# schematic1.net
KiCad netlist of a schematic drawn in EAGLE
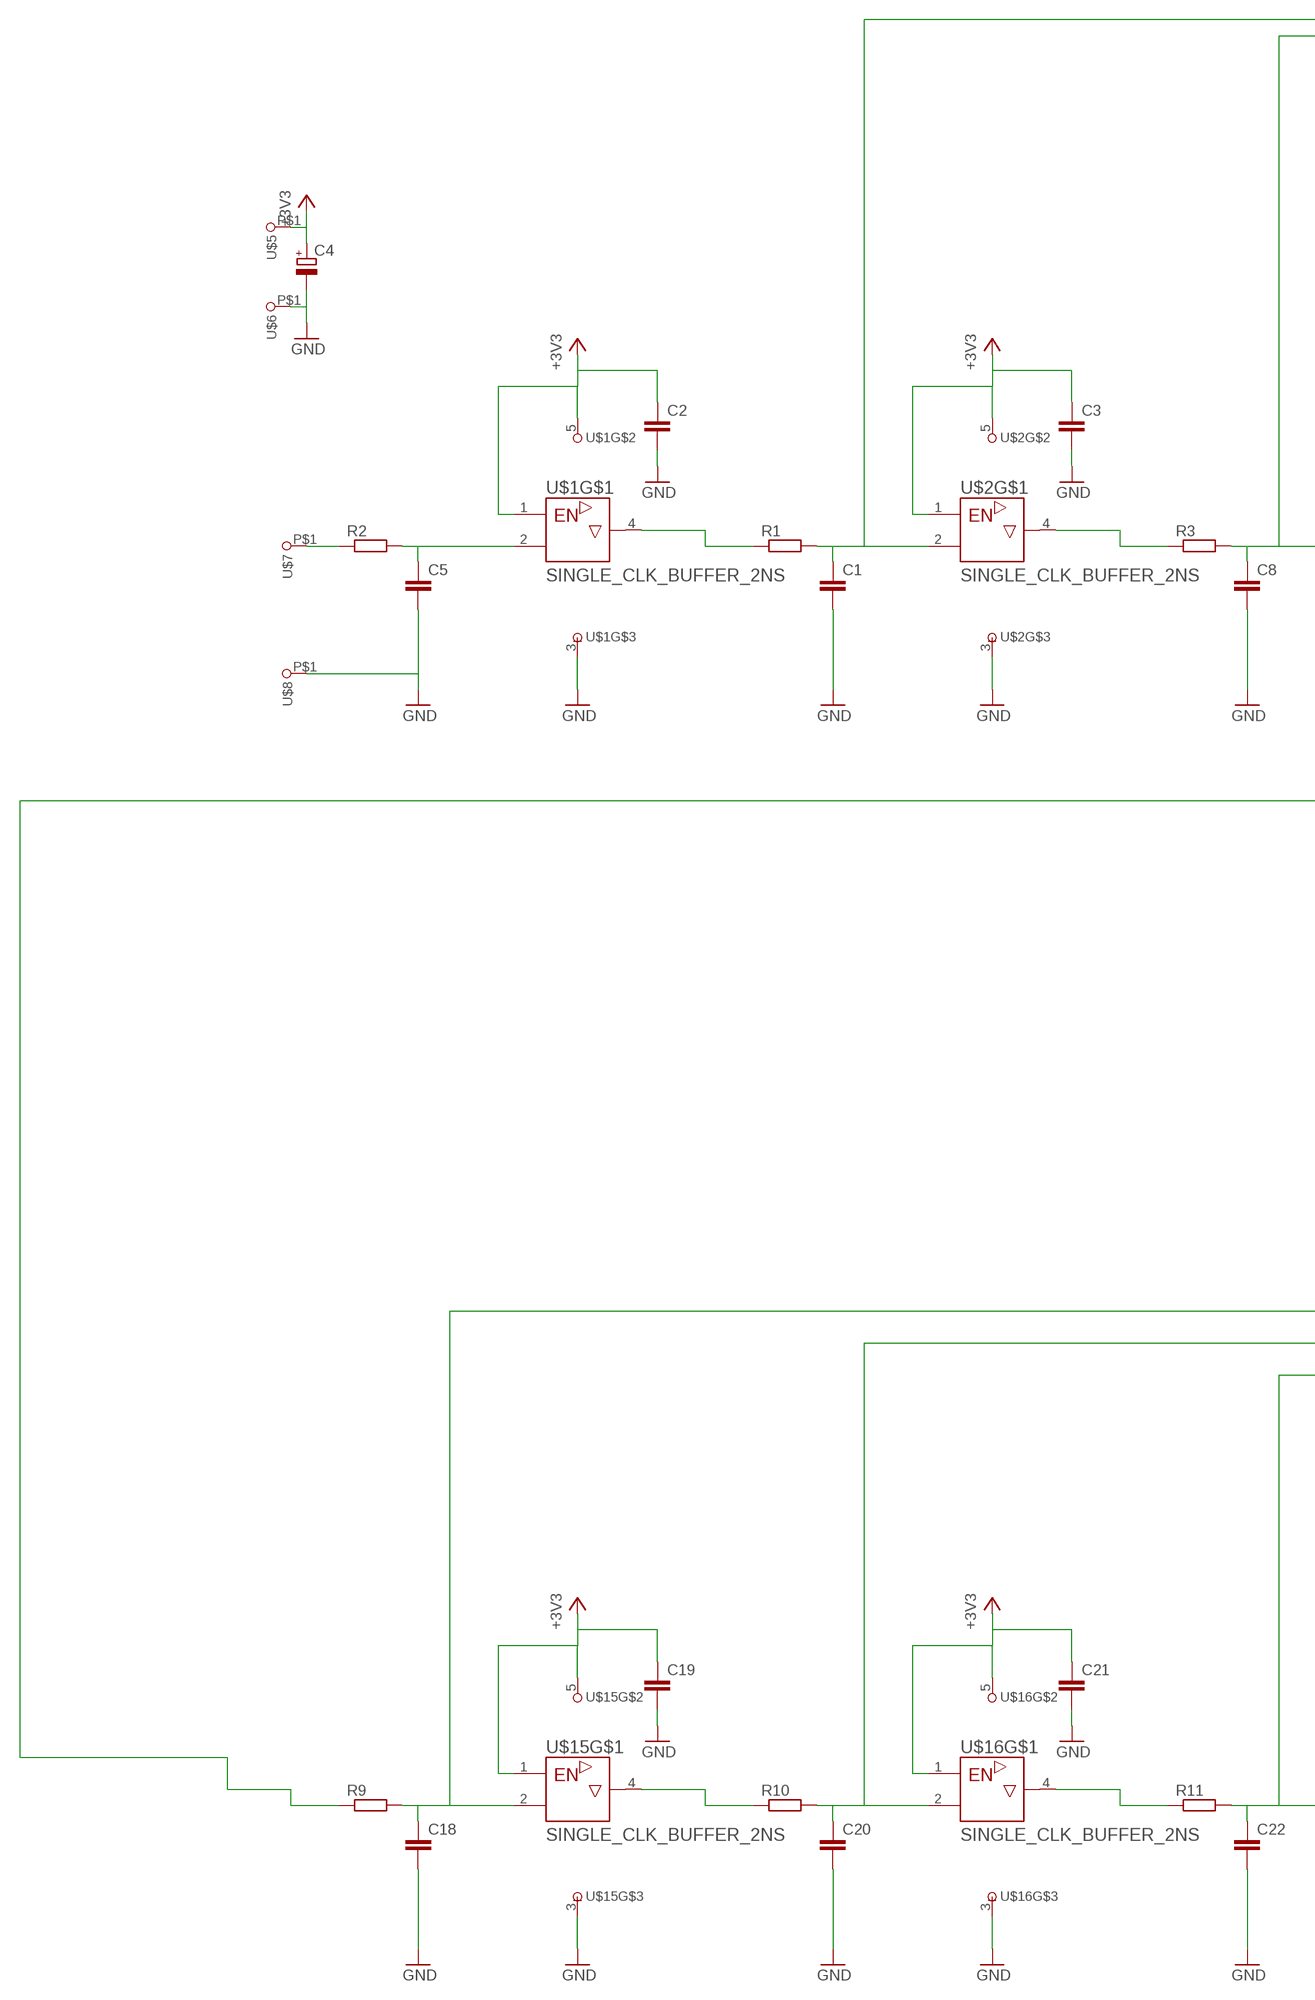
[diagram p0: schematic, sheet 1, part 1 of 2]
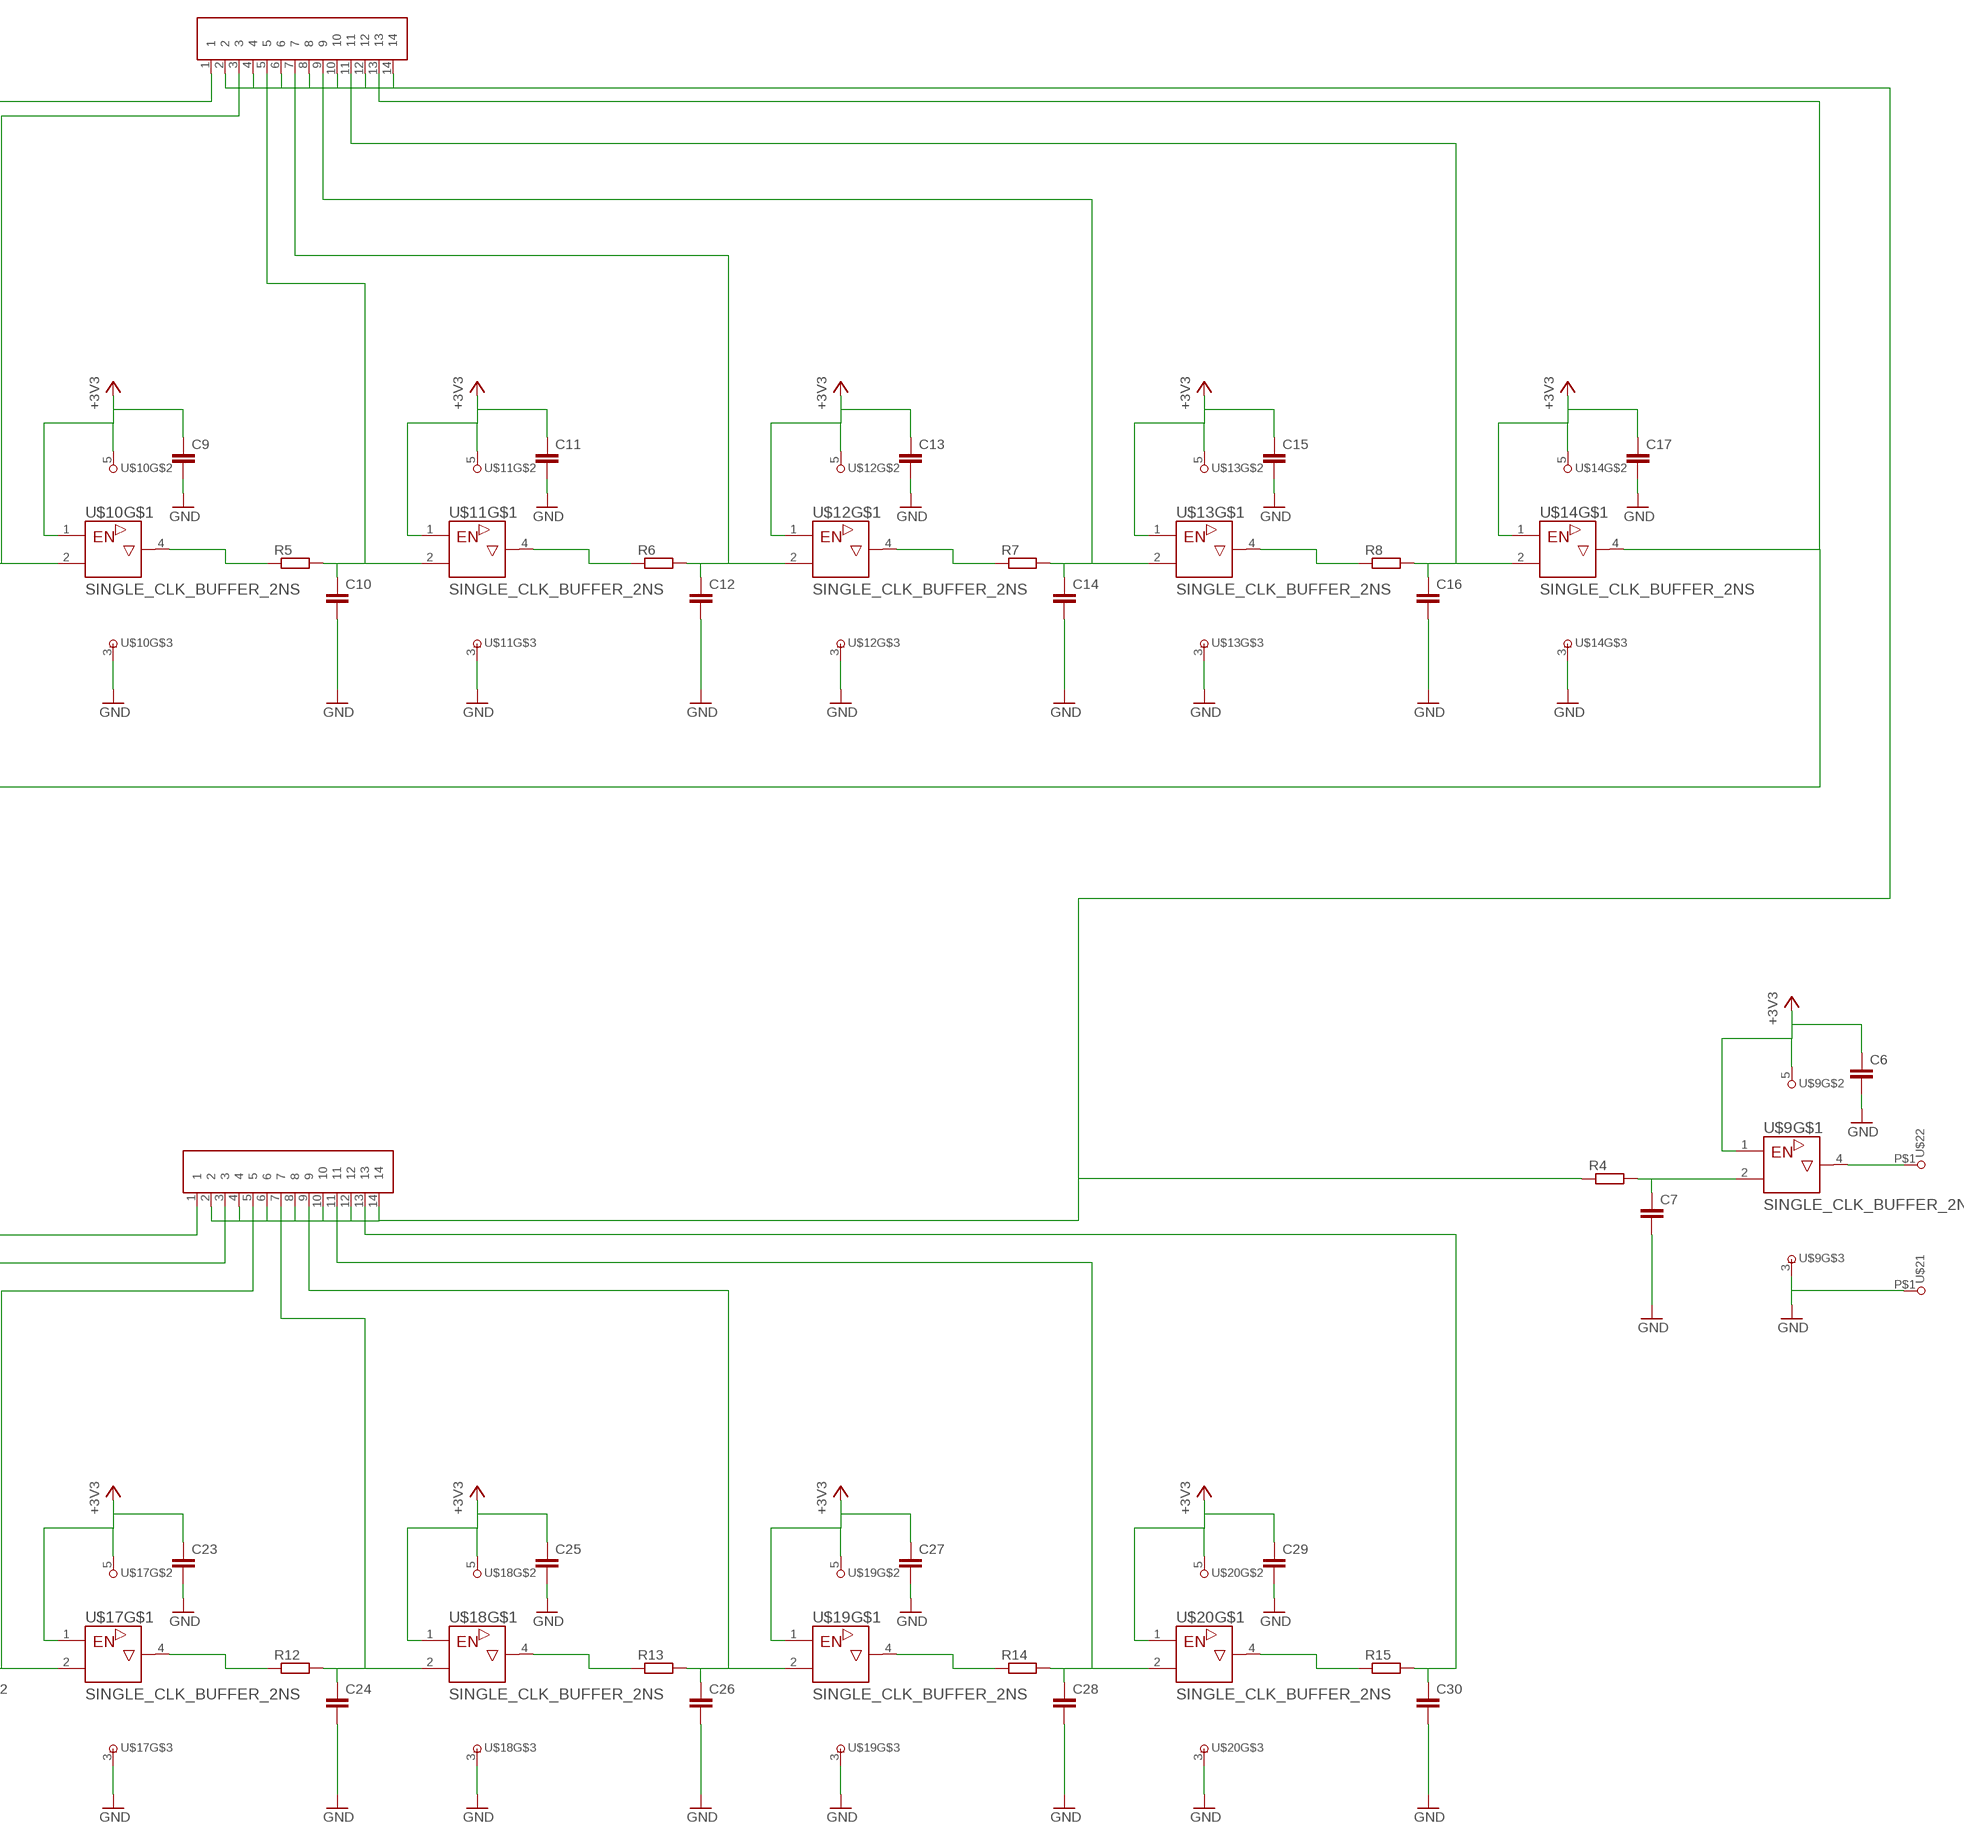
[diagram p1: schematic, sheet 1, part 2 of 2]

(export (version "E")
  (design (tool "Eeschema 10.0.6"))
  (components
    (comp (ref "C1")
      (value "C-EUC0603")
      (footprint "eagle-import:C0603")
      (libsource (lib "eagle-import") (part "C-EUC0603"))
    )
    (comp (ref "C2")
      (value "C-EUC0805")
      (footprint "eagle-import:C0805")
      (libsource (lib "eagle-import") (part "C-EUC0805"))
    )
    (comp (ref "C3")
      (value "C-EUC0805")
      (footprint "eagle-import:C0805")
      (libsource (lib "eagle-import") (part "C-EUC0805"))
    )
    (comp (ref "C4")
      (value "CPOL-EUSMCD")
      (footprint "eagle-import:SMC_D")
      (libsource (lib "eagle-import") (part "CPOL-EUSMCD"))
    )
    (comp (ref "C5")
      (value "C-EUC0603")
      (footprint "eagle-import:C0603")
      (libsource (lib "eagle-import") (part "C-EUC0603"))
    )
    (comp (ref "C6")
      (value "C-EUC0805")
      (footprint "eagle-import:C0805")
      (libsource (lib "eagle-import") (part "C-EUC0805"))
    )
    (comp (ref "C7")
      (value "C-EUC0603")
      (footprint "eagle-import:C0603")
      (libsource (lib "eagle-import") (part "C-EUC0603"))
    )
    (comp (ref "C8")
      (value "C-EUC0603")
      (footprint "eagle-import:C0603")
      (libsource (lib "eagle-import") (part "C-EUC0603"))
    )
    (comp (ref "C9")
      (value "C-EUC0805")
      (footprint "eagle-import:C0805")
      (libsource (lib "eagle-import") (part "C-EUC0805"))
    )
    (comp (ref "C10")
      (value "C-EUC0603")
      (footprint "eagle-import:C0603")
      (libsource (lib "eagle-import") (part "C-EUC0603"))
    )
    (comp (ref "C11")
      (value "C-EUC0805")
      (footprint "eagle-import:C0805")
      (libsource (lib "eagle-import") (part "C-EUC0805"))
    )
    (comp (ref "C12")
      (value "C-EUC0603")
      (footprint "eagle-import:C0603")
      (libsource (lib "eagle-import") (part "C-EUC0603"))
    )
    (comp (ref "C13")
      (value "C-EUC0805")
      (footprint "eagle-import:C0805")
      (libsource (lib "eagle-import") (part "C-EUC0805"))
    )
    (comp (ref "C14")
      (value "C-EUC0603")
      (footprint "eagle-import:C0603")
      (libsource (lib "eagle-import") (part "C-EUC0603"))
    )
    (comp (ref "C15")
      (value "C-EUC0805")
      (footprint "eagle-import:C0805")
      (libsource (lib "eagle-import") (part "C-EUC0805"))
    )
    (comp (ref "C16")
      (value "C-EUC0603")
      (footprint "eagle-import:C0603")
      (libsource (lib "eagle-import") (part "C-EUC0603"))
    )
    (comp (ref "C17")
      (value "C-EUC0805")
      (footprint "eagle-import:C0805")
      (libsource (lib "eagle-import") (part "C-EUC0805"))
    )
    (comp (ref "C18")
      (value "C-EUC0603")
      (footprint "eagle-import:C0603")
      (libsource (lib "eagle-import") (part "C-EUC0603"))
    )
    (comp (ref "C19")
      (value "C-EUC0805")
      (footprint "eagle-import:C0805")
      (libsource (lib "eagle-import") (part "C-EUC0805"))
    )
    (comp (ref "C20")
      (value "C-EUC0603")
      (footprint "eagle-import:C0603")
      (libsource (lib "eagle-import") (part "C-EUC0603"))
    )
    (comp (ref "C21")
      (value "C-EUC0805")
      (footprint "eagle-import:C0805")
      (libsource (lib "eagle-import") (part "C-EUC0805"))
    )
    (comp (ref "C22")
      (value "C-EUC0603")
      (footprint "eagle-import:C0603")
      (libsource (lib "eagle-import") (part "C-EUC0603"))
    )
    (comp (ref "C23")
      (value "C-EUC0805")
      (footprint "eagle-import:C0805")
      (libsource (lib "eagle-import") (part "C-EUC0805"))
    )
    (comp (ref "C24")
      (value "C-EUC0603")
      (footprint "eagle-import:C0603")
      (libsource (lib "eagle-import") (part "C-EUC0603"))
    )
    (comp (ref "C25")
      (value "C-EUC0805")
      (footprint "eagle-import:C0805")
      (libsource (lib "eagle-import") (part "C-EUC0805"))
    )
    (comp (ref "C26")
      (value "C-EUC0603")
      (footprint "eagle-import:C0603")
      (libsource (lib "eagle-import") (part "C-EUC0603"))
    )
    (comp (ref "C27")
      (value "C-EUC0805")
      (footprint "eagle-import:C0805")
      (libsource (lib "eagle-import") (part "C-EUC0805"))
    )
    (comp (ref "C28")
      (value "C-EUC0603")
      (footprint "eagle-import:C0603")
      (libsource (lib "eagle-import") (part "C-EUC0603"))
    )
    (comp (ref "C29")
      (value "C-EUC0805")
      (footprint "eagle-import:C0805")
      (libsource (lib "eagle-import") (part "C-EUC0805"))
    )
    (comp (ref "C30")
      (value "C-EUC0603")
      (footprint "eagle-import:C0603")
      (libsource (lib "eagle-import") (part "C-EUC0603"))
    )
    (comp (ref "R1")
      (value "R-EU_R0603")
      (footprint "eagle-import:R0603")
      (libsource (lib "eagle-import") (part "R-EU_R0603"))
    )
    (comp (ref "R2")
      (value "R-EU_R0603")
      (footprint "eagle-import:R0603")
      (libsource (lib "eagle-import") (part "R-EU_R0603"))
    )
    (comp (ref "R3")
      (value "R-EU_R0603")
      (footprint "eagle-import:R0603")
      (libsource (lib "eagle-import") (part "R-EU_R0603"))
    )
    (comp (ref "R4")
      (value "R-EU_R0603")
      (footprint "eagle-import:R0603")
      (libsource (lib "eagle-import") (part "R-EU_R0603"))
    )
    (comp (ref "R5")
      (value "R-EU_R0603")
      (footprint "eagle-import:R0603")
      (libsource (lib "eagle-import") (part "R-EU_R0603"))
    )
    (comp (ref "R6")
      (value "R-EU_R0603")
      (footprint "eagle-import:R0603")
      (libsource (lib "eagle-import") (part "R-EU_R0603"))
    )
    (comp (ref "R7")
      (value "R-EU_R0603")
      (footprint "eagle-import:R0603")
      (libsource (lib "eagle-import") (part "R-EU_R0603"))
    )
    (comp (ref "R8")
      (value "R-EU_R0603")
      (footprint "eagle-import:R0603")
      (libsource (lib "eagle-import") (part "R-EU_R0603"))
    )
    (comp (ref "R9")
      (value "R-EU_R0603")
      (footprint "eagle-import:R0603")
      (libsource (lib "eagle-import") (part "R-EU_R0603"))
    )
    (comp (ref "R10")
      (value "R-EU_R0603")
      (footprint "eagle-import:R0603")
      (libsource (lib "eagle-import") (part "R-EU_R0603"))
    )
    (comp (ref "R11")
      (value "R-EU_R0603")
      (footprint "eagle-import:R0603")
      (libsource (lib "eagle-import") (part "R-EU_R0603"))
    )
    (comp (ref "R12")
      (value "R-EU_R0603")
      (footprint "eagle-import:R0603")
      (libsource (lib "eagle-import") (part "R-EU_R0603"))
    )
    (comp (ref "R13")
      (value "R-EU_R0603")
      (footprint "eagle-import:R0603")
      (libsource (lib "eagle-import") (part "R-EU_R0603"))
    )
    (comp (ref "R14")
      (value "R-EU_R0603")
      (footprint "eagle-import:R0603")
      (libsource (lib "eagle-import") (part "R-EU_R0603"))
    )
    (comp (ref "R15")
      (value "R-EU_R0603")
      (footprint "eagle-import:R0603")
      (libsource (lib "eagle-import") (part "R-EU_R0603"))
    )
    (comp (ref "U$1")
      (value "SINGLE_CLK_BUFFER_2NS")
      (footprint "eagle-import:DCK")
      (libsource (lib "eagle-import") (part "SINGLE_CLK_BUFFER_2NS"))
    )
    (comp (ref "U$2")
      (value "SINGLE_CLK_BUFFER_2NS")
      (footprint "eagle-import:DCK")
      (libsource (lib "eagle-import") (part "SINGLE_CLK_BUFFER_2NS"))
    )
    (comp (ref "U$3")
      (value "2X7SMD_HEADER")
      (footprint "eagle-import:2X14SMDPADS")
      (libsource (lib "eagle-import") (part "2X7SMD_HEADER"))
    )
    (comp (ref "U$4")
      (value "2X7SMD_HEADER")
      (footprint "eagle-import:2X14SMDPADS")
      (libsource (lib "eagle-import") (part "2X7SMD_HEADER"))
    )
    (comp (ref "U$5")
      (value "BIGGOPAD")
      (footprint "eagle-import:BIGGOPAD")
      (libsource (lib "eagle-import") (part "BIGGOPAD"))
    )
    (comp (ref "U$6")
      (value "BIGGOPAD")
      (footprint "eagle-import:BIGGOPAD")
      (libsource (lib "eagle-import") (part "BIGGOPAD"))
    )
    (comp (ref "U$7")
      (value "BIGGOPAD")
      (footprint "eagle-import:BIGGOPAD")
      (libsource (lib "eagle-import") (part "BIGGOPAD"))
    )
    (comp (ref "U$8")
      (value "BIGGOPAD")
      (footprint "eagle-import:BIGGOPAD")
      (libsource (lib "eagle-import") (part "BIGGOPAD"))
    )
    (comp (ref "U$9")
      (value "SINGLE_CLK_BUFFER_2NS")
      (footprint "eagle-import:DCK")
      (libsource (lib "eagle-import") (part "SINGLE_CLK_BUFFER_2NS"))
    )
    (comp (ref "U$10")
      (value "SINGLE_CLK_BUFFER_2NS")
      (footprint "eagle-import:DCK")
      (libsource (lib "eagle-import") (part "SINGLE_CLK_BUFFER_2NS"))
    )
    (comp (ref "U$11")
      (value "SINGLE_CLK_BUFFER_2NS")
      (footprint "eagle-import:DCK")
      (libsource (lib "eagle-import") (part "SINGLE_CLK_BUFFER_2NS"))
    )
    (comp (ref "U$12")
      (value "SINGLE_CLK_BUFFER_2NS")
      (footprint "eagle-import:DCK")
      (libsource (lib "eagle-import") (part "SINGLE_CLK_BUFFER_2NS"))
    )
    (comp (ref "U$13")
      (value "SINGLE_CLK_BUFFER_2NS")
      (footprint "eagle-import:DCK")
      (libsource (lib "eagle-import") (part "SINGLE_CLK_BUFFER_2NS"))
    )
    (comp (ref "U$14")
      (value "SINGLE_CLK_BUFFER_2NS")
      (footprint "eagle-import:DCK")
      (libsource (lib "eagle-import") (part "SINGLE_CLK_BUFFER_2NS"))
    )
    (comp (ref "U$15")
      (value "SINGLE_CLK_BUFFER_2NS")
      (footprint "eagle-import:DCK")
      (libsource (lib "eagle-import") (part "SINGLE_CLK_BUFFER_2NS"))
    )
    (comp (ref "U$16")
      (value "SINGLE_CLK_BUFFER_2NS")
      (footprint "eagle-import:DCK")
      (libsource (lib "eagle-import") (part "SINGLE_CLK_BUFFER_2NS"))
    )
    (comp (ref "U$17")
      (value "SINGLE_CLK_BUFFER_2NS")
      (footprint "eagle-import:DCK")
      (libsource (lib "eagle-import") (part "SINGLE_CLK_BUFFER_2NS"))
    )
    (comp (ref "U$18")
      (value "SINGLE_CLK_BUFFER_2NS")
      (footprint "eagle-import:DCK")
      (libsource (lib "eagle-import") (part "SINGLE_CLK_BUFFER_2NS"))
    )
    (comp (ref "U$19")
      (value "SINGLE_CLK_BUFFER_2NS")
      (footprint "eagle-import:DCK")
      (libsource (lib "eagle-import") (part "SINGLE_CLK_BUFFER_2NS"))
    )
    (comp (ref "U$20")
      (value "SINGLE_CLK_BUFFER_2NS")
      (footprint "eagle-import:DCK")
      (libsource (lib "eagle-import") (part "SINGLE_CLK_BUFFER_2NS"))
    )
    (comp (ref "U$21")
      (value "BIGGOPAD")
      (footprint "eagle-import:BIGGOPAD")
      (libsource (lib "eagle-import") (part "BIGGOPAD"))
    )
    (comp (ref "U$22")
      (value "BIGGOPAD")
      (footprint "eagle-import:BIGGOPAD")
      (libsource (lib "eagle-import") (part "BIGGOPAD"))
    )
  )
  (nets
    (net (code "1") (name "+3V3") (class "Default")
      (node (ref "C11") (pin "1") (pinfunction "1_1") (pintype "passive"))
      (node (ref "C13") (pin "1") (pinfunction "1_1") (pintype "passive"))
      (node (ref "C15") (pin "1") (pinfunction "1_1") (pintype "passive"))
      (node (ref "C17") (pin "1") (pinfunction "1_1") (pintype "passive"))
      (node (ref "C19") (pin "1") (pinfunction "1_1") (pintype "passive"))
      (node (ref "C2") (pin "1") (pinfunction "1_1") (pintype "passive"))
      (node (ref "C21") (pin "1") (pinfunction "1_1") (pintype "passive"))
      (node (ref "C23") (pin "1") (pinfunction "1_1") (pintype "passive"))
      (node (ref "C25") (pin "1") (pinfunction "1_1") (pintype "passive"))
      (node (ref "C27") (pin "1") (pinfunction "1_1") (pintype "passive"))
      (node (ref "C29") (pin "1") (pinfunction "1_1") (pintype "passive"))
      (node (ref "C3") (pin "1") (pinfunction "1_1") (pintype "passive"))
      (node (ref "C4") (pin "+") (pinfunction "+_+") (pintype "passive"))
      (node (ref "C6") (pin "1") (pinfunction "1_1") (pintype "passive"))
      (node (ref "C9") (pin "1") (pinfunction "1_1") (pintype "passive"))
      (node (ref "U$1") (pin "1") (pinfunction "G_1") (pintype "input"))
      (node (ref "U$1") (pin "5") (pinfunction "+UB_5") (pintype "power_in"))
      (node (ref "U$10") (pin "1") (pinfunction "G_1") (pintype "input"))
      (node (ref "U$10") (pin "5") (pinfunction "+UB_5") (pintype "power_in"))
      (node (ref "U$11") (pin "1") (pinfunction "G_1") (pintype "input"))
      (node (ref "U$11") (pin "5") (pinfunction "+UB_5") (pintype "power_in"))
      (node (ref "U$12") (pin "1") (pinfunction "G_1") (pintype "input"))
      (node (ref "U$12") (pin "5") (pinfunction "+UB_5") (pintype "power_in"))
      (node (ref "U$13") (pin "1") (pinfunction "G_1") (pintype "input"))
      (node (ref "U$13") (pin "5") (pinfunction "+UB_5") (pintype "power_in"))
      (node (ref "U$14") (pin "1") (pinfunction "G_1") (pintype "input"))
      (node (ref "U$14") (pin "5") (pinfunction "+UB_5") (pintype "power_in"))
      (node (ref "U$15") (pin "1") (pinfunction "G_1") (pintype "input"))
      (node (ref "U$15") (pin "5") (pinfunction "+UB_5") (pintype "power_in"))
      (node (ref "U$16") (pin "1") (pinfunction "G_1") (pintype "input"))
      (node (ref "U$16") (pin "5") (pinfunction "+UB_5") (pintype "power_in"))
      (node (ref "U$17") (pin "1") (pinfunction "G_1") (pintype "input"))
      (node (ref "U$17") (pin "5") (pinfunction "+UB_5") (pintype "power_in"))
      (node (ref "U$18") (pin "1") (pinfunction "G_1") (pintype "input"))
      (node (ref "U$18") (pin "5") (pinfunction "+UB_5") (pintype "power_in"))
      (node (ref "U$19") (pin "1") (pinfunction "G_1") (pintype "input"))
      (node (ref "U$19") (pin "5") (pinfunction "+UB_5") (pintype "power_in"))
      (node (ref "U$2") (pin "1") (pinfunction "G_1") (pintype "input"))
      (node (ref "U$2") (pin "5") (pinfunction "+UB_5") (pintype "power_in"))
      (node (ref "U$20") (pin "1") (pinfunction "G_1") (pintype "input"))
      (node (ref "U$20") (pin "5") (pinfunction "+UB_5") (pintype "power_in"))
      (node (ref "U$5") (pin "P$1") (pinfunction "+UB_P$1") (pintype "power_in"))
      (node (ref "U$9") (pin "1") (pinfunction "G_1") (pintype "input"))
      (node (ref "U$9") (pin "5") (pinfunction "+UB_5") (pintype "power_in"))
    )
    (net (code "2") (name "GND") (class "Default")
      (node (ref "C1") (pin "2") (pinfunction "2_2") (pintype "passive"))
      (node (ref "C10") (pin "2") (pinfunction "2_2") (pintype "passive"))
      (node (ref "C11") (pin "2") (pinfunction "2_2") (pintype "passive"))
      (node (ref "C12") (pin "2") (pinfunction "2_2") (pintype "passive"))
      (node (ref "C13") (pin "2") (pinfunction "2_2") (pintype "passive"))
      (node (ref "C14") (pin "2") (pinfunction "2_2") (pintype "passive"))
      (node (ref "C15") (pin "2") (pinfunction "2_2") (pintype "passive"))
      (node (ref "C16") (pin "2") (pinfunction "2_2") (pintype "passive"))
      (node (ref "C17") (pin "2") (pinfunction "2_2") (pintype "passive"))
      (node (ref "C18") (pin "2") (pinfunction "2_2") (pintype "passive"))
      (node (ref "C19") (pin "2") (pinfunction "2_2") (pintype "passive"))
      (node (ref "C2") (pin "2") (pinfunction "2_2") (pintype "passive"))
      (node (ref "C20") (pin "2") (pinfunction "2_2") (pintype "passive"))
      (node (ref "C21") (pin "2") (pinfunction "2_2") (pintype "passive"))
      (node (ref "C22") (pin "2") (pinfunction "2_2") (pintype "passive"))
      (node (ref "C23") (pin "2") (pinfunction "2_2") (pintype "passive"))
      (node (ref "C24") (pin "2") (pinfunction "2_2") (pintype "passive"))
      (node (ref "C25") (pin "2") (pinfunction "2_2") (pintype "passive"))
      (node (ref "C26") (pin "2") (pinfunction "2_2") (pintype "passive"))
      (node (ref "C27") (pin "2") (pinfunction "2_2") (pintype "passive"))
      (node (ref "C28") (pin "2") (pinfunction "2_2") (pintype "passive"))
      (node (ref "C29") (pin "2") (pinfunction "2_2") (pintype "passive"))
      (node (ref "C3") (pin "2") (pinfunction "2_2") (pintype "passive"))
      (node (ref "C30") (pin "2") (pinfunction "2_2") (pintype "passive"))
      (node (ref "C4") (pin "-") (pinfunction "-_-") (pintype "passive"))
      (node (ref "C5") (pin "2") (pinfunction "2_2") (pintype "passive"))
      (node (ref "C6") (pin "2") (pinfunction "2_2") (pintype "passive"))
      (node (ref "C7") (pin "2") (pinfunction "2_2") (pintype "passive"))
      (node (ref "C8") (pin "2") (pinfunction "2_2") (pintype "passive"))
      (node (ref "C9") (pin "2") (pinfunction "2_2") (pintype "passive"))
      (node (ref "U$1") (pin "3") (pinfunction "-UB_3") (pintype "power_in"))
      (node (ref "U$10") (pin "3") (pinfunction "-UB_3") (pintype "power_in"))
      (node (ref "U$11") (pin "3") (pinfunction "-UB_3") (pintype "power_in"))
      (node (ref "U$12") (pin "3") (pinfunction "-UB_3") (pintype "power_in"))
      (node (ref "U$13") (pin "3") (pinfunction "-UB_3") (pintype "power_in"))
      (node (ref "U$14") (pin "3") (pinfunction "-UB_3") (pintype "power_in"))
      (node (ref "U$15") (pin "3") (pinfunction "-UB_3") (pintype "power_in"))
      (node (ref "U$16") (pin "3") (pinfunction "-UB_3") (pintype "power_in"))
      (node (ref "U$17") (pin "3") (pinfunction "-UB_3") (pintype "power_in"))
      (node (ref "U$18") (pin "3") (pinfunction "-UB_3") (pintype "power_in"))
      (node (ref "U$19") (pin "3") (pinfunction "-UB_3") (pintype "power_in"))
      (node (ref "U$2") (pin "3") (pinfunction "-UB_3") (pintype "power_in"))
      (node (ref "U$20") (pin "3") (pinfunction "-UB_3") (pintype "power_in"))
      (node (ref "U$21") (pin "P$1") (pinfunction "+UB_P$1") (pintype "power_in"))
      (node (ref "U$6") (pin "P$1") (pinfunction "+UB_P$1") (pintype "power_in"))
      (node (ref "U$8") (pin "P$1") (pinfunction "+UB_P$1") (pintype "power_in"))
      (node (ref "U$9") (pin "3") (pinfunction "-UB_3") (pintype "power_in"))
    )
    (net (code "3") (name "Net-(C30-Pad1)") (class "Default")
      (node (ref "C30") (pin "1") (pinfunction "1_1") (pintype "passive"))
      (node (ref "R15") (pin "2") (pinfunction "2_2") (pintype "passive"))
      (node (ref "U$4") (pin "13") (pinfunction "13_13") (pintype "input"))
    )
    (net (code "4") (name "Net-(R4-Pad1)") (class "Default")
      (node (ref "R4") (pin "1") (pinfunction "1_1") (pintype "passive"))
      (node (ref "U$3") (pin "10") (pinfunction "10_10") (pintype "input"))
      (node (ref "U$3") (pin "12") (pinfunction "12_12") (pintype "input"))
      (node (ref "U$3") (pin "14") (pinfunction "14_14") (pintype "input"))
      (node (ref "U$3") (pin "2") (pinfunction "2_2") (pintype "input"))
      (node (ref "U$3") (pin "4") (pinfunction "4_4") (pintype "input"))
      (node (ref "U$3") (pin "6") (pinfunction "6_6") (pintype "input"))
      (node (ref "U$3") (pin "8") (pinfunction "8_8") (pintype "input"))
      (node (ref "U$4") (pin "10") (pinfunction "10_10") (pintype "input"))
      (node (ref "U$4") (pin "12") (pinfunction "12_12") (pintype "input"))
      (node (ref "U$4") (pin "14") (pinfunction "14_14") (pintype "input"))
      (node (ref "U$4") (pin "2") (pinfunction "2_2") (pintype "input"))
      (node (ref "U$4") (pin "4") (pinfunction "4_4") (pintype "input"))
      (node (ref "U$4") (pin "6") (pinfunction "6_6") (pintype "input"))
      (node (ref "U$4") (pin "8") (pinfunction "8_8") (pintype "input"))
    )
    (net (code "5") (name "Net-(U$1A-A)") (class "Default")
      (node (ref "C5") (pin "1") (pinfunction "1_1") (pintype "passive"))
      (node (ref "R2") (pin "2") (pinfunction "2_2") (pintype "passive"))
      (node (ref "U$1") (pin "2") (pinfunction "A_2") (pintype "input"))
    )
    (net (code "6") (name "Net-(U$1A-Y)") (class "Default")
      (node (ref "R1") (pin "1") (pinfunction "1_1") (pintype "passive"))
      (node (ref "U$1") (pin "4") (pinfunction "Y_4") (pintype "tri_state"))
    )
    (net (code "7") (name "Net-(U$2A-A)") (class "Default")
      (node (ref "C1") (pin "1") (pinfunction "1_1") (pintype "passive"))
      (node (ref "R1") (pin "2") (pinfunction "2_2") (pintype "passive"))
      (node (ref "U$2") (pin "2") (pinfunction "A_2") (pintype "input"))
      (node (ref "U$3") (pin "1") (pinfunction "1_1") (pintype "input"))
    )
    (net (code "8") (name "Net-(U$2A-Y)") (class "Default")
      (node (ref "R3") (pin "1") (pinfunction "1_1") (pintype "passive"))
      (node (ref "U$2") (pin "4") (pinfunction "Y_4") (pintype "tri_state"))
    )
    (net (code "9") (name "Net-(U$7-+UB)") (class "Default")
      (node (ref "R2") (pin "1") (pinfunction "1_1") (pintype "passive"))
      (node (ref "U$7") (pin "P$1") (pinfunction "+UB_P$1") (pintype "power_in"))
    )
    (net (code "10") (name "Net-(U$9A-A)") (class "Default")
      (node (ref "C7") (pin "1") (pinfunction "1_1") (pintype "passive"))
      (node (ref "R4") (pin "2") (pinfunction "2_2") (pintype "passive"))
      (node (ref "U$9") (pin "2") (pinfunction "A_2") (pintype "input"))
    )
    (net (code "11") (name "Net-(U$10A-A)") (class "Default")
      (node (ref "C8") (pin "1") (pinfunction "1_1") (pintype "passive"))
      (node (ref "R3") (pin "2") (pinfunction "2_2") (pintype "passive"))
      (node (ref "U$10") (pin "2") (pinfunction "A_2") (pintype "input"))
      (node (ref "U$3") (pin "3") (pinfunction "3_3") (pintype "input"))
    )
    (net (code "12") (name "Net-(U$10A-Y)") (class "Default")
      (node (ref "R5") (pin "1") (pinfunction "1_1") (pintype "passive"))
      (node (ref "U$10") (pin "4") (pinfunction "Y_4") (pintype "tri_state"))
    )
    (net (code "13") (name "Net-(U$11A-A)") (class "Default")
      (node (ref "C10") (pin "1") (pinfunction "1_1") (pintype "passive"))
      (node (ref "R5") (pin "2") (pinfunction "2_2") (pintype "passive"))
      (node (ref "U$11") (pin "2") (pinfunction "A_2") (pintype "input"))
      (node (ref "U$3") (pin "5") (pinfunction "5_5") (pintype "input"))
    )
    (net (code "14") (name "Net-(U$11A-Y)") (class "Default")
      (node (ref "R6") (pin "1") (pinfunction "1_1") (pintype "passive"))
      (node (ref "U$11") (pin "4") (pinfunction "Y_4") (pintype "tri_state"))
    )
    (net (code "15") (name "Net-(U$12A-A)") (class "Default")
      (node (ref "C12") (pin "1") (pinfunction "1_1") (pintype "passive"))
      (node (ref "R6") (pin "2") (pinfunction "2_2") (pintype "passive"))
      (node (ref "U$12") (pin "2") (pinfunction "A_2") (pintype "input"))
      (node (ref "U$3") (pin "7") (pinfunction "7_7") (pintype "input"))
    )
    (net (code "16") (name "Net-(U$12A-Y)") (class "Default")
      (node (ref "R7") (pin "1") (pinfunction "1_1") (pintype "passive"))
      (node (ref "U$12") (pin "4") (pinfunction "Y_4") (pintype "tri_state"))
    )
    (net (code "17") (name "Net-(U$13A-A)") (class "Default")
      (node (ref "C14") (pin "1") (pinfunction "1_1") (pintype "passive"))
      (node (ref "R7") (pin "2") (pinfunction "2_2") (pintype "passive"))
      (node (ref "U$13") (pin "2") (pinfunction "A_2") (pintype "input"))
      (node (ref "U$3") (pin "9") (pinfunction "9_9") (pintype "input"))
    )
    (net (code "18") (name "Net-(U$13A-Y)") (class "Default")
      (node (ref "R8") (pin "1") (pinfunction "1_1") (pintype "passive"))
      (node (ref "U$13") (pin "4") (pinfunction "Y_4") (pintype "tri_state"))
    )
    (net (code "19") (name "Net-(U$14A-A)") (class "Default")
      (node (ref "C16") (pin "1") (pinfunction "1_1") (pintype "passive"))
      (node (ref "R8") (pin "2") (pinfunction "2_2") (pintype "passive"))
      (node (ref "U$14") (pin "2") (pinfunction "A_2") (pintype "input"))
      (node (ref "U$3") (pin "11") (pinfunction "11_11") (pintype "input"))
    )
    (net (code "20") (name "Net-(U$14A-Y)") (class "Default")
      (node (ref "R9") (pin "1") (pinfunction "1_1") (pintype "passive"))
      (node (ref "U$14") (pin "4") (pinfunction "Y_4") (pintype "tri_state"))
      (node (ref "U$3") (pin "13") (pinfunction "13_13") (pintype "input"))
    )
    (net (code "21") (name "Net-(U$15A-A)") (class "Default")
      (node (ref "C18") (pin "1") (pinfunction "1_1") (pintype "passive"))
      (node (ref "R9") (pin "2") (pinfunction "2_2") (pintype "passive"))
      (node (ref "U$15") (pin "2") (pinfunction "A_2") (pintype "input"))
      (node (ref "U$4") (pin "1") (pinfunction "1_1") (pintype "input"))
    )
    (net (code "22") (name "Net-(U$15A-Y)") (class "Default")
      (node (ref "R10") (pin "1") (pinfunction "1_1") (pintype "passive"))
      (node (ref "U$15") (pin "4") (pinfunction "Y_4") (pintype "tri_state"))
    )
    (net (code "23") (name "Net-(U$16A-A)") (class "Default")
      (node (ref "C20") (pin "1") (pinfunction "1_1") (pintype "passive"))
      (node (ref "R10") (pin "2") (pinfunction "2_2") (pintype "passive"))
      (node (ref "U$16") (pin "2") (pinfunction "A_2") (pintype "input"))
      (node (ref "U$4") (pin "3") (pinfunction "3_3") (pintype "input"))
    )
    (net (code "24") (name "Net-(U$16A-Y)") (class "Default")
      (node (ref "R11") (pin "1") (pinfunction "1_1") (pintype "passive"))
      (node (ref "U$16") (pin "4") (pinfunction "Y_4") (pintype "tri_state"))
    )
    (net (code "25") (name "Net-(U$17A-A)") (class "Default")
      (node (ref "C22") (pin "1") (pinfunction "1_1") (pintype "passive"))
      (node (ref "R11") (pin "2") (pinfunction "2_2") (pintype "passive"))
      (node (ref "U$17") (pin "2") (pinfunction "A_2") (pintype "input"))
      (node (ref "U$4") (pin "5") (pinfunction "5_5") (pintype "input"))
    )
    (net (code "26") (name "Net-(U$17A-Y)") (class "Default")
      (node (ref "R12") (pin "1") (pinfunction "1_1") (pintype "passive"))
      (node (ref "U$17") (pin "4") (pinfunction "Y_4") (pintype "tri_state"))
    )
    (net (code "27") (name "Net-(U$18A-A)") (class "Default")
      (node (ref "C24") (pin "1") (pinfunction "1_1") (pintype "passive"))
      (node (ref "R12") (pin "2") (pinfunction "2_2") (pintype "passive"))
      (node (ref "U$18") (pin "2") (pinfunction "A_2") (pintype "input"))
      (node (ref "U$4") (pin "7") (pinfunction "7_7") (pintype "input"))
    )
    (net (code "28") (name "Net-(U$18A-Y)") (class "Default")
      (node (ref "R13") (pin "1") (pinfunction "1_1") (pintype "passive"))
      (node (ref "U$18") (pin "4") (pinfunction "Y_4") (pintype "tri_state"))
    )
    (net (code "29") (name "Net-(U$19A-A)") (class "Default")
      (node (ref "C26") (pin "1") (pinfunction "1_1") (pintype "passive"))
      (node (ref "R13") (pin "2") (pinfunction "2_2") (pintype "passive"))
      (node (ref "U$19") (pin "2") (pinfunction "A_2") (pintype "input"))
      (node (ref "U$4") (pin "9") (pinfunction "9_9") (pintype "input"))
    )
    (net (code "30") (name "Net-(U$19A-Y)") (class "Default")
      (node (ref "R14") (pin "1") (pinfunction "1_1") (pintype "passive"))
      (node (ref "U$19") (pin "4") (pinfunction "Y_4") (pintype "tri_state"))
    )
    (net (code "31") (name "Net-(U$20A-A)") (class "Default")
      (node (ref "C28") (pin "1") (pinfunction "1_1") (pintype "passive"))
      (node (ref "R14") (pin "2") (pinfunction "2_2") (pintype "passive"))
      (node (ref "U$20") (pin "2") (pinfunction "A_2") (pintype "input"))
      (node (ref "U$4") (pin "11") (pinfunction "11_11") (pintype "input"))
    )
    (net (code "32") (name "Net-(U$20A-Y)") (class "Default")
      (node (ref "R15") (pin "1") (pinfunction "1_1") (pintype "passive"))
      (node (ref "U$20") (pin "4") (pinfunction "Y_4") (pintype "tri_state"))
    )
    (net (code "33") (name "Net-(U$22-+UB)") (class "Default")
      (node (ref "U$22") (pin "P$1") (pinfunction "+UB_P$1") (pintype "power_in"))
      (node (ref "U$9") (pin "4") (pinfunction "Y_4") (pintype "tri_state"))
    )
  )
)
